# dashboard.net
KiCad netlist of a schematic drawn in EAGLE
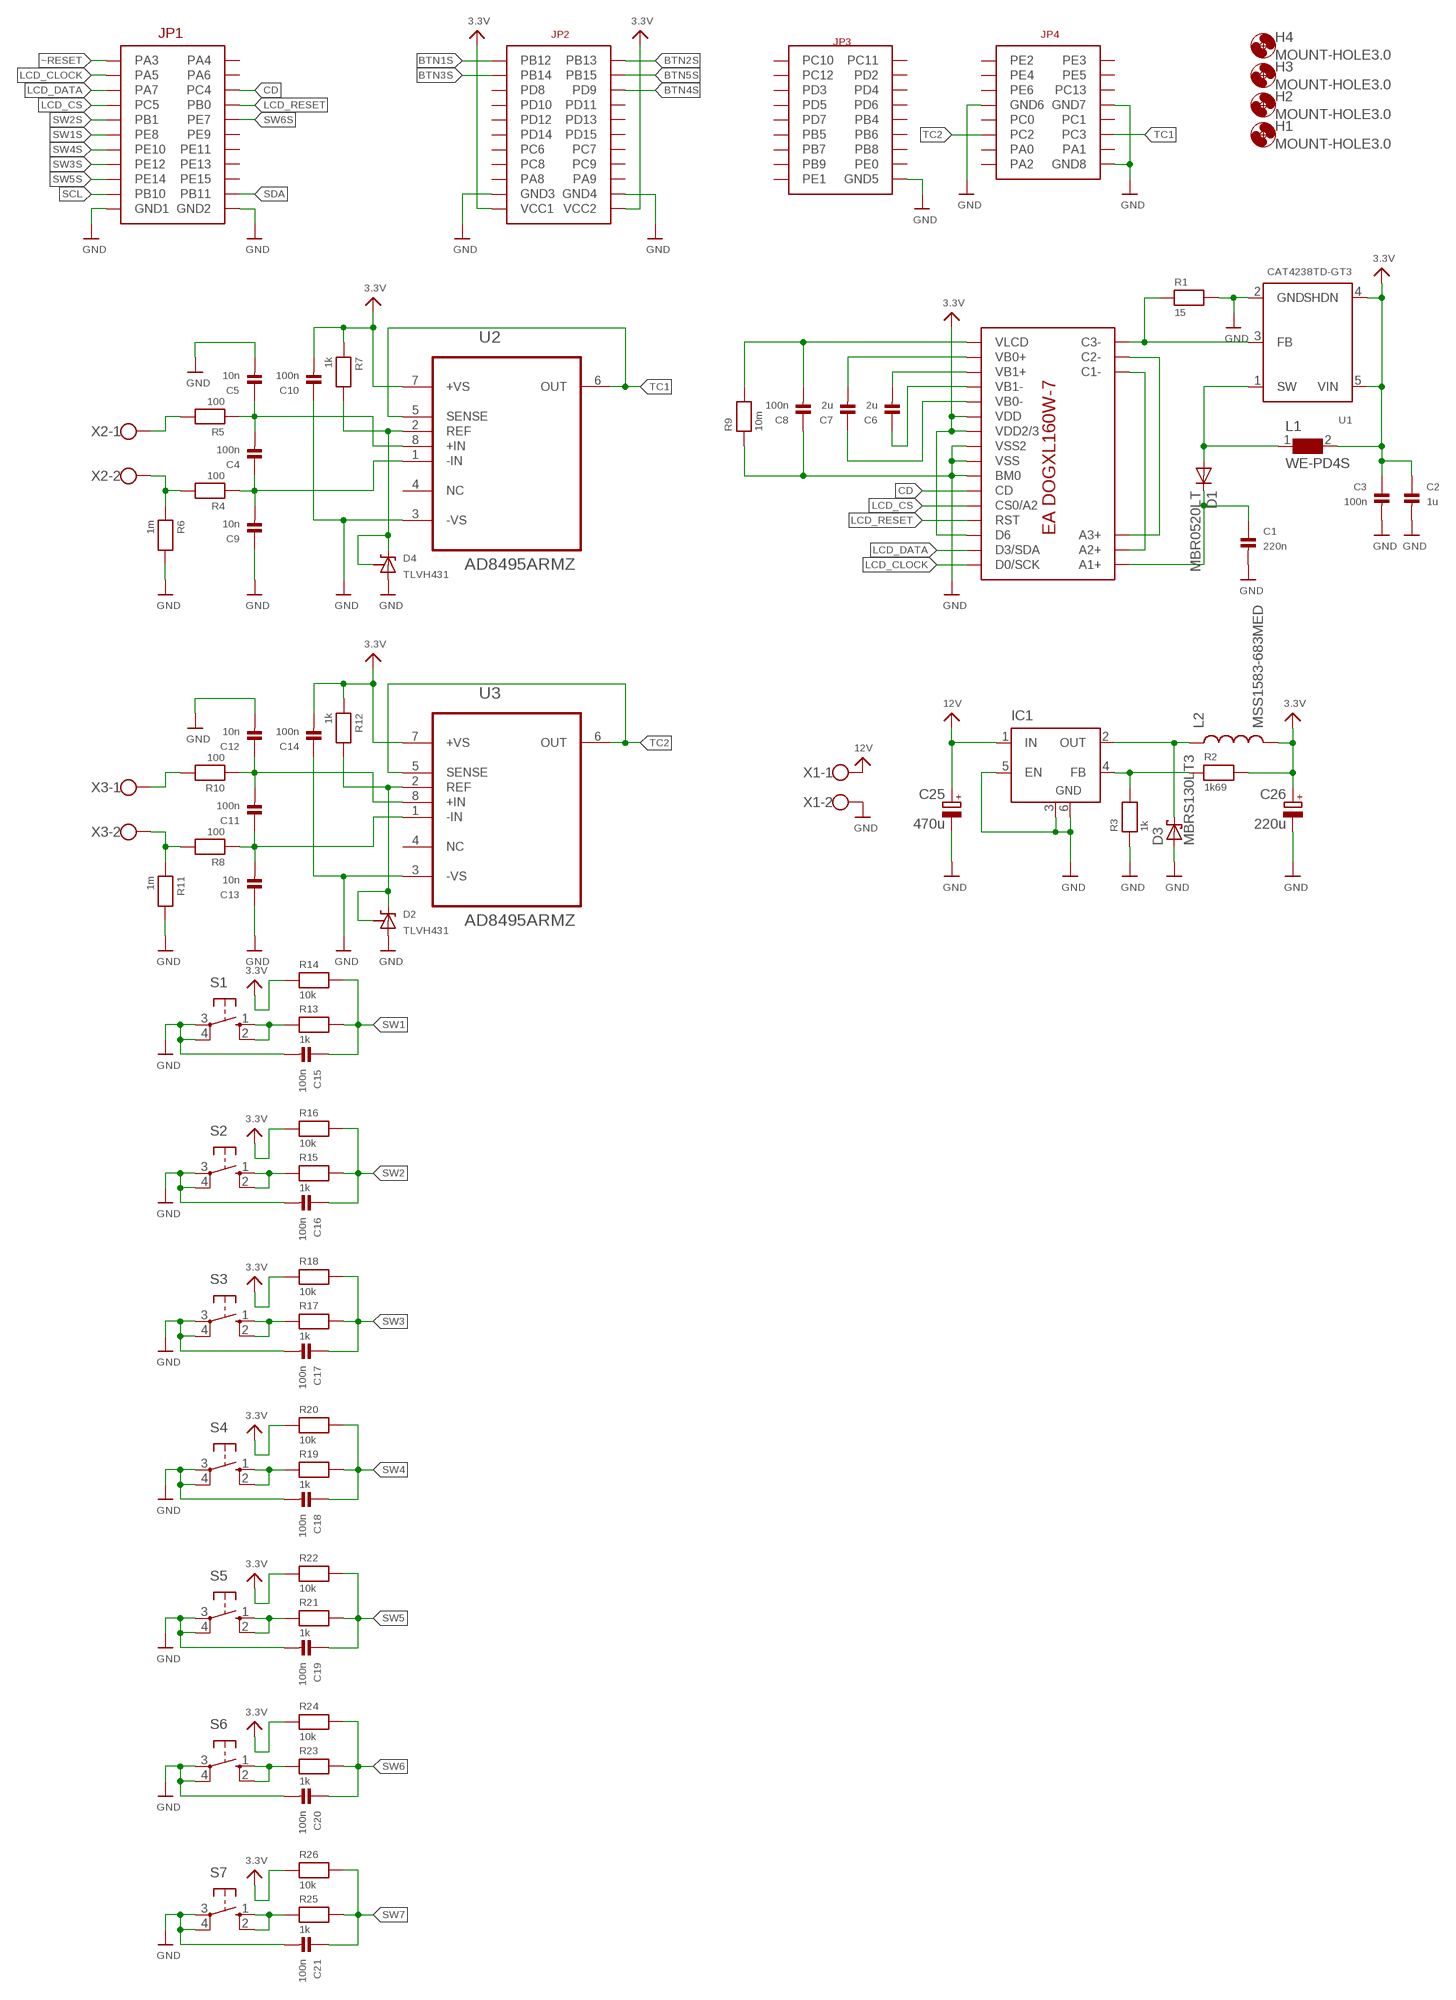
[diagram p0: schematic, sheet 1]

(export (version "E")
  (design (tool "Eeschema 10.0.6"))
  (components
    (comp (ref "C1")
      (value "220n")
      (footprint "eagle-import:_0805")
      (libsource (lib "eagle-import") (part "CAP_CERAMIC_0805"))
    )
    (comp (ref "C2")
      (value "1u")
      (footprint "eagle-import:_0805")
      (libsource (lib "eagle-import") (part "CAP_CERAMIC_0805"))
    )
    (comp (ref "C3")
      (value "100n")
      (footprint "eagle-import:_0603")
      (libsource (lib "eagle-import") (part "CAP_CERAMIC_0603"))
    )
    (comp (ref "C4")
      (value "100n")
      (footprint "eagle-import:_0603")
      (libsource (lib "eagle-import") (part "CAP_CERAMIC_0603"))
    )
    (comp (ref "C5")
      (value "10n")
      (footprint "eagle-import:_0603")
      (libsource (lib "eagle-import") (part "CAP_CERAMIC_0603"))
    )
    (comp (ref "C6")
      (value "2u")
      (footprint "eagle-import:_0805")
      (libsource (lib "eagle-import") (part "CAP_CERAMIC_0805"))
    )
    (comp (ref "C7")
      (value "2u")
      (footprint "eagle-import:_0805")
      (libsource (lib "eagle-import") (part "CAP_CERAMIC_0805"))
    )
    (comp (ref "C8")
      (value "100n")
      (footprint "eagle-import:_0603")
      (libsource (lib "eagle-import") (part "CAP_CERAMIC_0603"))
    )
    (comp (ref "C9")
      (value "10n")
      (footprint "eagle-import:_0603")
      (libsource (lib "eagle-import") (part "CAP_CERAMIC_0603"))
    )
    (comp (ref "C10")
      (value "100n")
      (footprint "eagle-import:_0603")
      (libsource (lib "eagle-import") (part "CAP_CERAMIC_0603"))
    )
    (comp (ref "C11")
      (value "100n")
      (footprint "eagle-import:_0603")
      (libsource (lib "eagle-import") (part "CAP_CERAMIC_0603"))
    )
    (comp (ref "C12")
      (value "10n")
      (footprint "eagle-import:_0603")
      (libsource (lib "eagle-import") (part "CAP_CERAMIC_0603"))
    )
    (comp (ref "C13")
      (value "10n")
      (footprint "eagle-import:_0603")
      (libsource (lib "eagle-import") (part "CAP_CERAMIC_0603"))
    )
    (comp (ref "C14")
      (value "100n")
      (footprint "eagle-import:_0603")
      (libsource (lib "eagle-import") (part "CAP_CERAMIC_0603"))
    )
    (comp (ref "C15")
      (value "100n")
      (footprint "eagle-import:_0603")
      (libsource (lib "eagle-import") (part "CAP_CERAMIC_0603"))
    )
    (comp (ref "C16")
      (value "100n")
      (footprint "eagle-import:_0603")
      (libsource (lib "eagle-import") (part "CAP_CERAMIC_0603"))
    )
    (comp (ref "C17")
      (value "100n")
      (footprint "eagle-import:_0603")
      (libsource (lib "eagle-import") (part "CAP_CERAMIC_0603"))
    )
    (comp (ref "C18")
      (value "100n")
      (footprint "eagle-import:_0603")
      (libsource (lib "eagle-import") (part "CAP_CERAMIC_0603"))
    )
    (comp (ref "C19")
      (value "100n")
      (footprint "eagle-import:_0603")
      (libsource (lib "eagle-import") (part "CAP_CERAMIC_0603"))
    )
    (comp (ref "C20")
      (value "100n")
      (footprint "eagle-import:_0603")
      (libsource (lib "eagle-import") (part "CAP_CERAMIC_0603"))
    )
    (comp (ref "C21")
      (value "100n")
      (footprint "eagle-import:_0603")
      (libsource (lib "eagle-import") (part "CAP_CERAMIC_0603"))
    )
    (comp (ref "C25")
      (value "470u")
      (footprint "eagle-import:153CLV-1012")
      (libsource (lib "eagle-import") (part "CPOL-EU153CLV-1012"))
    )
    (comp (ref "C26")
      (value "220u")
      (footprint "eagle-import:153CLV-1012")
      (libsource (lib "eagle-import") (part "CPOL-EU153CLV-1012"))
    )
    (comp (ref "D1")
      (value "MBR0520LT")
      (footprint "eagle-import:SOD123")
      (libsource (lib "eagle-import") (part "MBR0520LT"))
    )
    (comp (ref "D2")
      (value "TLVH431")
      (footprint "eagle-import:SOT23-R")
      (libsource (lib "eagle-import") (part "SHUNT-VREF"))
    )
    (comp (ref "D3")
      (value "MBRS130LT3")
      (footprint "eagle-import:SMB")
      (libsource (lib "eagle-import") (part "MBRS130LT3"))
    )
    (comp (ref "D4")
      (value "TLVH431")
      (footprint "eagle-import:SOT23-R")
      (libsource (lib "eagle-import") (part "SHUNT-VREF"))
    )
    (comp (ref "H1")
      (value "MOUNT-HOLE3.0")
      (footprint "eagle-import:3,0")
      (libsource (lib "eagle-import") (part "MOUNT-HOLE3.0"))
    )
    (comp (ref "H2")
      (value "MOUNT-HOLE3.0")
      (footprint "eagle-import:3,0")
      (libsource (lib "eagle-import") (part "MOUNT-HOLE3.0"))
    )
    (comp (ref "H3")
      (value "MOUNT-HOLE3.0")
      (footprint "eagle-import:3,0")
      (libsource (lib "eagle-import") (part "MOUNT-HOLE3.0"))
    )
    (comp (ref "H4")
      (value "MOUNT-HOLE3.0")
      (footprint "eagle-import:3,0")
      (libsource (lib "eagle-import") (part "MOUNT-HOLE3.0"))
    )
    (comp (ref "IC1")
      (value "LM2596S")
      (footprint "eagle-import:TO263-5")
      (libsource (lib "eagle-import") (part "LM2596S"))
    )
    (comp (ref "L1")
      (value "WE-PD4S")
      (footprint "eagle-import:S")
      (fields (field (name "MPN") "7445501"))
      (libsource (lib "eagle-import") (part "WE-PD4_S-7445501"))
    )
    (comp (ref "L2")
      (value "MSS1583-683MED")
      (footprint "eagle-import:CDRH125")
      (libsource (lib "eagle-import") (part "INDUCTORPWR"))
    )
    (comp (ref "R1")
      (value "15")
      (footprint "eagle-import:_0603")
      (libsource (lib "eagle-import") (part "RESISTOR_0603"))
    )
    (comp (ref "R2")
      (value "1k69")
      (footprint "eagle-import:_0603")
      (libsource (lib "eagle-import") (part "RESISTOR_0603"))
    )
    (comp (ref "R3")
      (value "1k")
      (footprint "eagle-import:_0603")
      (libsource (lib "eagle-import") (part "RESISTOR_0603"))
    )
    (comp (ref "R4")
      (value "100")
      (footprint "eagle-import:_0603")
      (libsource (lib "eagle-import") (part "RESISTOR_0603"))
    )
    (comp (ref "R5")
      (value "100")
      (footprint "eagle-import:_0603")
      (libsource (lib "eagle-import") (part "RESISTOR_0603"))
    )
    (comp (ref "R6")
      (value "1m")
      (footprint "eagle-import:_0603")
      (libsource (lib "eagle-import") (part "RESISTOR_0603"))
    )
    (comp (ref "R7")
      (value "1k")
      (footprint "eagle-import:_0603")
      (libsource (lib "eagle-import") (part "RESISTOR_0603"))
    )
    (comp (ref "R8")
      (value "100")
      (footprint "eagle-import:_0603")
      (libsource (lib "eagle-import") (part "RESISTOR_0603"))
    )
    (comp (ref "R9")
      (value "10m")
      (footprint "eagle-import:_0805")
      (libsource (lib "eagle-import") (part "RESISTOR_0805"))
    )
    (comp (ref "R10")
      (value "100")
      (footprint "eagle-import:_0603")
      (libsource (lib "eagle-import") (part "RESISTOR_0603"))
    )
    (comp (ref "R11")
      (value "1m")
      (footprint "eagle-import:_0603")
      (libsource (lib "eagle-import") (part "RESISTOR_0603"))
    )
    (comp (ref "R12")
      (value "1k")
      (footprint "eagle-import:_0603")
      (libsource (lib "eagle-import") (part "RESISTOR_0603"))
    )
    (comp (ref "R13")
      (value "1k")
      (footprint "eagle-import:_0603")
      (libsource (lib "eagle-import") (part "RESISTOR_0603"))
    )
    (comp (ref "R14")
      (value "10k")
      (footprint "eagle-import:_0603")
      (libsource (lib "eagle-import") (part "RESISTOR_0603"))
    )
    (comp (ref "R15")
      (value "1k")
      (footprint "eagle-import:_0603")
      (libsource (lib "eagle-import") (part "RESISTOR_0603"))
    )
    (comp (ref "R16")
      (value "10k")
      (footprint "eagle-import:_0603")
      (libsource (lib "eagle-import") (part "RESISTOR_0603"))
    )
    (comp (ref "R17")
      (value "1k")
      (footprint "eagle-import:_0603")
      (libsource (lib "eagle-import") (part "RESISTOR_0603"))
    )
    (comp (ref "R18")
      (value "10k")
      (footprint "eagle-import:_0603")
      (libsource (lib "eagle-import") (part "RESISTOR_0603"))
    )
    (comp (ref "R19")
      (value "1k")
      (footprint "eagle-import:_0603")
      (libsource (lib "eagle-import") (part "RESISTOR_0603"))
    )
    (comp (ref "R20")
      (value "10k")
      (footprint "eagle-import:_0603")
      (libsource (lib "eagle-import") (part "RESISTOR_0603"))
    )
    (comp (ref "R21")
      (value "1k")
      (footprint "eagle-import:_0603")
      (libsource (lib "eagle-import") (part "RESISTOR_0603"))
    )
    (comp (ref "R22")
      (value "10k")
      (footprint "eagle-import:_0603")
      (libsource (lib "eagle-import") (part "RESISTOR_0603"))
    )
    (comp (ref "R23")
      (value "1k")
      (footprint "eagle-import:_0603")
      (libsource (lib "eagle-import") (part "RESISTOR_0603"))
    )
    (comp (ref "R24")
      (value "10k")
      (footprint "eagle-import:_0603")
      (libsource (lib "eagle-import") (part "RESISTOR_0603"))
    )
    (comp (ref "R25")
      (value "1k")
      (footprint "eagle-import:_0603")
      (libsource (lib "eagle-import") (part "RESISTOR_0603"))
    )
    (comp (ref "R26")
      (value "10k")
      (footprint "eagle-import:_0603")
      (libsource (lib "eagle-import") (part "RESISTOR_0603"))
    )
    (comp (ref "S1")
      (value "10-XX")
      (footprint "eagle-import:B3F-10XX")
      (fields (field (name "MPN") "B3F-1000"))
      (libsource (lib "eagle-import") (part "10-XX"))
    )
    (comp (ref "S2")
      (value "10-XX")
      (footprint "eagle-import:B3F-10XX")
      (fields (field (name "MPN") "B3F-1000"))
      (libsource (lib "eagle-import") (part "10-XX"))
    )
    (comp (ref "S3")
      (value "10-XX")
      (footprint "eagle-import:B3F-10XX")
      (fields (field (name "MPN") "B3F-1000"))
      (libsource (lib "eagle-import") (part "10-XX"))
    )
    (comp (ref "S4")
      (value "10-XX")
      (footprint "eagle-import:B3F-10XX")
      (fields (field (name "MPN") "B3F-1000"))
      (libsource (lib "eagle-import") (part "10-XX"))
    )
    (comp (ref "S5")
      (value "10-XX")
      (footprint "eagle-import:B3F-10XX")
      (fields (field (name "MPN") "B3F-1000"))
      (libsource (lib "eagle-import") (part "10-XX"))
    )
    (comp (ref "S6")
      (value "10-XX")
      (footprint "eagle-import:B3F-10XX")
      (fields (field (name "MPN") "B3F-1000"))
      (libsource (lib "eagle-import") (part "10-XX"))
    )
    (comp (ref "S7")
      (value "10-XX")
      (footprint "eagle-import:B3F-10XX")
      (fields (field (name "MPN") "B3F-1000"))
      (libsource (lib "eagle-import") (part "10-XX"))
    )
    (comp (ref "U$1")
      (value "CPU-BOARD")
      (footprint "eagle-import:CPU-BOARD-JP1")
      (libsource (lib "eagle-import") (part "CPU-BOARD"))
    )
    (comp (ref "U$10")
      (value "EA-DOGXL160W-7")
      (footprint "eagle-import:EA-DOGXL160W-7")
      (libsource (lib "eagle-import") (part "EA-DOGXL160W-7"))
    )
    (comp (ref "U1")
      (value "CAT4238TD-GT3")
      (footprint "eagle-import:SOT23-5")
      (libsource (lib "eagle-import") (part "FAN5331"))
    )
    (comp (ref "U2")
      (value "AD8495ARMZ")
      (footprint "eagle-import:SOP65P490X110-8N")
      (libsource (lib "eagle-import") (part "AD8495ARMZ"))
    )
    (comp (ref "U3")
      (value "AD8495ARMZ")
      (footprint "eagle-import:SOP65P490X110-8N")
      (libsource (lib "eagle-import") (part "AD8495ARMZ"))
    )
    (comp (ref "X1")
      (value "W237-102")
      (footprint "eagle-import:W237-102")
      (fields (field (name "MPN") "237-102"))
      (libsource (lib "eagle-import") (part "W237-102"))
    )
    (comp (ref "X2")
      (value "W237-102")
      (footprint "eagle-import:W237-102")
      (fields (field (name "MPN") "237-102"))
      (libsource (lib "eagle-import") (part "W237-102"))
    )
    (comp (ref "X3")
      (value "W237-102")
      (footprint "eagle-import:W237-102")
      (fields (field (name "MPN") "237-102"))
      (libsource (lib "eagle-import") (part "W237-102"))
    )
  )
  (nets
    (net (code "1") (name "/~{RESET}") (class "Default")
      (node (ref "U$1") (pin "P$1") (pinfunction "PA3_P$1") (pintype "bidirectional"))
    )
    (net (code "2") (name "3.3V") (class "Default")
      (node (ref "C10") (pin "2") (pinfunction "P$2_2") (pintype "passive"))
      (node (ref "C14") (pin "2") (pinfunction "P$2_2") (pintype "passive"))
      (node (ref "C2") (pin "1") (pinfunction "P$1_1") (pintype "passive"))
      (node (ref "C26") (pin "+") (pinfunction "+_+") (pintype "passive"))
      (node (ref "C3") (pin "1") (pinfunction "P$1_1") (pintype "passive"))
      (node (ref "L1") (pin "2") (pinfunction "2_2") (pintype "passive"))
      (node (ref "L2") (pin "2") (pinfunction "2_2") (pintype "passive"))
      (node (ref "R12") (pin "1") (pinfunction "1_1") (pintype "passive"))
      (node (ref "R14") (pin "1") (pinfunction "1_1") (pintype "passive"))
      (node (ref "R16") (pin "1") (pinfunction "1_1") (pintype "passive"))
      (node (ref "R18") (pin "1") (pinfunction "1_1") (pintype "passive"))
      (node (ref "R2") (pin "2") (pinfunction "2_2") (pintype "passive"))
      (node (ref "R20") (pin "1") (pinfunction "1_1") (pintype "passive"))
      (node (ref "R22") (pin "1") (pinfunction "1_1") (pintype "passive"))
      (node (ref "R24") (pin "1") (pinfunction "1_1") (pintype "passive"))
      (node (ref "R26") (pin "1") (pinfunction "1_1") (pintype "passive"))
      (node (ref "R7") (pin "1") (pinfunction "1_1") (pintype "passive"))
      (node (ref "U$1") (pin "P$43") (pinfunction "VCC1_P$43") (pintype "bidirectional"))
      (node (ref "U$1") (pin "P$44") (pinfunction "VCC2_P$44") (pintype "bidirectional"))
      (node (ref "U$10") (pin "P$22") (pinfunction "VDD_P$22") (pintype "bidirectional"))
      (node (ref "U$10") (pin "P$23") (pinfunction "VDD2/3_P$23") (pintype "bidirectional"))
      (node (ref "U$10") (pin "P$30") (pinfunction "D6_P$30") (pintype "bidirectional"))
      (node (ref "U1") (pin "4") (pinfunction "SHDN_4") (pintype "bidirectional"))
      (node (ref "U1") (pin "5") (pinfunction "VIN_5") (pintype "bidirectional"))
      (node (ref "U2") (pin "7") (pinfunction "+VS_7") (pintype "power_in"))
      (node (ref "U3") (pin "7") (pinfunction "+VS_7") (pintype "power_in"))
    )
    (net (code "3") (name "12V") (class "Default")
      (node (ref "C25") (pin "+") (pinfunction "+_+") (pintype "passive"))
      (node (ref "IC1") (pin "1") (pinfunction "IN_1") (pintype "input"))
      (node (ref "X1") (pin "1") (pinfunction "KL_1") (pintype "passive"))
    )
    (net (code "4") (name "BTN1S") (class "Default")
      (node (ref "U$1") (pin "P$23") (pinfunction "PB12_P$23") (pintype "bidirectional"))
    )
    (net (code "5") (name "BTN2S") (class "Default")
      (node (ref "U$1") (pin "P$24") (pinfunction "PB13_P$24") (pintype "bidirectional"))
    )
    (net (code "6") (name "BTN3S") (class "Default")
      (node (ref "U$1") (pin "P$25") (pinfunction "PB14_P$25") (pintype "bidirectional"))
    )
    (net (code "7") (name "BTN4S") (class "Default")
      (node (ref "U$1") (pin "P$28") (pinfunction "PD9_P$28") (pintype "bidirectional"))
    )
    (net (code "8") (name "BTN5S") (class "Default")
      (node (ref "U$1") (pin "P$26") (pinfunction "PB15_P$26") (pintype "bidirectional"))
    )
    (net (code "9") (name "CD") (class "Default")
      (node (ref "U$1") (pin "P$6") (pinfunction "PC4_P$6") (pintype "bidirectional"))
      (node (ref "U$10") (pin "P$27") (pinfunction "CD_P$27") (pintype "bidirectional"))
    )
    (net (code "10") (name "GND") (class "Default")
      (node (ref "C1") (pin "2") (pinfunction "P$2_2") (pintype "passive"))
      (node (ref "C10") (pin "1") (pinfunction "P$1_1") (pintype "passive"))
      (node (ref "C12") (pin "2") (pinfunction "P$2_2") (pintype "passive"))
      (node (ref "C13") (pin "1") (pinfunction "P$1_1") (pintype "passive"))
      (node (ref "C14") (pin "1") (pinfunction "P$1_1") (pintype "passive"))
      (node (ref "C15") (pin "2") (pinfunction "P$2_2") (pintype "passive"))
      (node (ref "C16") (pin "2") (pinfunction "P$2_2") (pintype "passive"))
      (node (ref "C17") (pin "2") (pinfunction "P$2_2") (pintype "passive"))
      (node (ref "C18") (pin "2") (pinfunction "P$2_2") (pintype "passive"))
      (node (ref "C19") (pin "2") (pinfunction "P$2_2") (pintype "passive"))
      (node (ref "C2") (pin "2") (pinfunction "P$2_2") (pintype "passive"))
      (node (ref "C20") (pin "2") (pinfunction "P$2_2") (pintype "passive"))
      (node (ref "C21") (pin "2") (pinfunction "P$2_2") (pintype "passive"))
      (node (ref "C25") (pin "-") (pinfunction "-_-") (pintype "passive"))
      (node (ref "C26") (pin "-") (pinfunction "-_-") (pintype "passive"))
      (node (ref "C3") (pin "2") (pinfunction "P$2_2") (pintype "passive"))
      (node (ref "C5") (pin "2") (pinfunction "P$2_2") (pintype "passive"))
      (node (ref "C8") (pin "1") (pinfunction "P$1_1") (pintype "passive"))
      (node (ref "C9") (pin "1") (pinfunction "P$1_1") (pintype "passive"))
      (node (ref "D2") (pin "3") (pinfunction "A_3") (pintype "passive"))
      (node (ref "D3") (pin "A") (pinfunction "A_A") (pintype "passive"))
      (node (ref "D4") (pin "3") (pinfunction "A_3") (pintype "passive"))
      (node (ref "IC1") (pin "3") (pinfunction "GND_3") (pintype "power_in"))
      (node (ref "IC1") (pin "5") (pinfunction "EN_5") (pintype "input"))
      (node (ref "IC1") (pin "6") (pinfunction "GND_6") (pintype "power_in"))
      (node (ref "R1") (pin "2") (pinfunction "2_2") (pintype "passive"))
      (node (ref "R11") (pin "2") (pinfunction "2_2") (pintype "passive"))
      (node (ref "R3") (pin "1") (pinfunction "1_1") (pintype "passive"))
      (node (ref "R6") (pin "2") (pinfunction "2_2") (pintype "passive"))
      (node (ref "R9") (pin "1") (pinfunction "1_1") (pintype "passive"))
      (node (ref "S1") (pin "3") (pinfunction "P_3") (pintype "passive"))
      (node (ref "S1") (pin "4") (pinfunction "P1_4") (pintype "passive"))
      (node (ref "S2") (pin "3") (pinfunction "P_3") (pintype "passive"))
      (node (ref "S2") (pin "4") (pinfunction "P1_4") (pintype "passive"))
      (node (ref "S3") (pin "3") (pinfunction "P_3") (pintype "passive"))
      (node (ref "S3") (pin "4") (pinfunction "P1_4") (pintype "passive"))
      (node (ref "S4") (pin "3") (pinfunction "P_3") (pintype "passive"))
      (node (ref "S4") (pin "4") (pinfunction "P1_4") (pintype "passive"))
      (node (ref "S5") (pin "3") (pinfunction "P_3") (pintype "passive"))
      (node (ref "S5") (pin "4") (pinfunction "P1_4") (pintype "passive"))
      (node (ref "S6") (pin "3") (pinfunction "P_3") (pintype "passive"))
      (node (ref "S6") (pin "4") (pinfunction "P1_4") (pintype "passive"))
      (node (ref "S7") (pin "3") (pinfunction "P_3") (pintype "passive"))
      (node (ref "S7") (pin "4") (pinfunction "P1_4") (pintype "passive"))
      (node (ref "U$1") (pin "P$19") (pinfunction "GND1_P$19") (pintype "bidirectional"))
      (node (ref "U$1") (pin "P$20") (pinfunction "GND2_P$20") (pintype "bidirectional"))
      (node (ref "U$1") (pin "P$41") (pinfunction "GND3_P$41") (pintype "bidirectional"))
      (node (ref "U$1") (pin "P$42") (pinfunction "GND4_P$42") (pintype "bidirectional"))
      (node (ref "U$1") (pin "P$62") (pinfunction "GND5_P$62") (pintype "bidirectional"))
      (node (ref "U$1") (pin "P$69") (pinfunction "GND6_P$69") (pintype "bidirectional"))
      (node (ref "U$1") (pin "P$70") (pinfunction "GND7_P$70") (pintype "bidirectional"))
      (node (ref "U$1") (pin "P$78") (pinfunction "GND8_P$78") (pintype "bidirectional"))
      (node (ref "U$10") (pin "P$24") (pinfunction "VSS2_P$24") (pintype "bidirectional"))
      (node (ref "U$10") (pin "P$25") (pinfunction "VSS_P$25") (pintype "bidirectional"))
      (node (ref "U$10") (pin "P$26") (pinfunction "BM0_P$26") (pintype "bidirectional"))
      (node (ref "U1") (pin "2") (pinfunction "GND_2") (pintype "bidirectional"))
      (node (ref "U2") (pin "3") (pinfunction "-VS_3") (pintype "power_in"))
      (node (ref "U3") (pin "3") (pinfunction "-VS_3") (pintype "power_in"))
      (node (ref "X1") (pin "2") (pinfunction "KL_2") (pintype "passive"))
    )
    (net (code "11") (name "LCD_CLOCK") (class "Default")
      (node (ref "U$1") (pin "P$3") (pinfunction "PA5_P$3") (pintype "bidirectional"))
      (node (ref "U$10") (pin "P$32") (pinfunction "D0/SCK_P$32") (pintype "bidirectional"))
    )
    (net (code "12") (name "LCD_CS") (class "Default")
      (node (ref "U$1") (pin "P$7") (pinfunction "PC5_P$7") (pintype "bidirectional"))
      (node (ref "U$10") (pin "P$28") (pinfunction "CS0/A2_P$28") (pintype "bidirectional"))
    )
    (net (code "13") (name "LCD_DATA") (class "Default")
      (node (ref "U$1") (pin "P$5") (pinfunction "PA7_P$5") (pintype "bidirectional"))
      (node (ref "U$10") (pin "P$31") (pinfunction "D3/SDA_P$31") (pintype "bidirectional"))
    )
    (net (code "14") (name "LCD_RESET") (class "Default")
      (node (ref "U$1") (pin "P$8") (pinfunction "PB0_P$8") (pintype "bidirectional"))
      (node (ref "U$10") (pin "P$29") (pinfunction "RST_P$29") (pintype "bidirectional"))
    )
    (net (code "15") (name "Net-(C1-P$1)") (class "Default")
      (node (ref "C1") (pin "1") (pinfunction "P$1_1") (pintype "passive"))
      (node (ref "D1") (pin "C") (pinfunction "C_C") (pintype "passive"))
      (node (ref "U$10") (pin "P$1") (pinfunction "A1+_P$1") (pintype "bidirectional"))
    )
    (net (code "16") (name "Net-(C4-P$1)") (class "Default")
      (node (ref "C4") (pin "1") (pinfunction "P$1_1") (pintype "passive"))
      (node (ref "C9") (pin "2") (pinfunction "P$2_2") (pintype "passive"))
      (node (ref "R4") (pin "1") (pinfunction "1_1") (pintype "passive"))
      (node (ref "U2") (pin "1") (pinfunction "-IN_1") (pintype "input"))
    )
    (net (code "17") (name "Net-(C4-P$2)") (class "Default")
      (node (ref "C4") (pin "2") (pinfunction "P$2_2") (pintype "passive"))
      (node (ref "C5") (pin "1") (pinfunction "P$1_1") (pintype "passive"))
      (node (ref "R5") (pin "1") (pinfunction "1_1") (pintype "passive"))
      (node (ref "U2") (pin "8") (pinfunction "+IN_8") (pintype "input"))
    )
    (net (code "18") (name "Net-(C6-P$1)") (class "Default")
      (node (ref "C6") (pin "1") (pinfunction "P$1_1") (pintype "passive"))
      (node (ref "U$10") (pin "P$20") (pinfunction "VB1-_P$20") (pintype "bidirectional"))
    )
    (net (code "19") (name "Net-(C6-P$2)") (class "Default")
      (node (ref "C6") (pin "2") (pinfunction "P$2_2") (pintype "passive"))
      (node (ref "U$10") (pin "P$19") (pinfunction "VB1+_P$19") (pintype "bidirectional"))
    )
    (net (code "20") (name "Net-(C7-P$1)") (class "Default")
      (node (ref "C7") (pin "1") (pinfunction "P$1_1") (pintype "passive"))
      (node (ref "U$10") (pin "P$21") (pinfunction "VB0-_P$21") (pintype "bidirectional"))
    )
    (net (code "21") (name "Net-(C7-P$2)") (class "Default")
      (node (ref "C7") (pin "2") (pinfunction "P$2_2") (pintype "passive"))
      (node (ref "U$10") (pin "P$18") (pinfunction "VB0+_P$18") (pintype "bidirectional"))
    )
    (net (code "22") (name "Net-(C8-P$2)") (class "Default")
      (node (ref "C8") (pin "2") (pinfunction "P$2_2") (pintype "passive"))
      (node (ref "R9") (pin "2") (pinfunction "2_2") (pintype "passive"))
      (node (ref "U$10") (pin "P$17") (pinfunction "VLCD_P$17") (pintype "bidirectional"))
    )
    (net (code "23") (name "Net-(C11-P$1)") (class "Default")
      (node (ref "C11") (pin "1") (pinfunction "P$1_1") (pintype "passive"))
      (node (ref "C13") (pin "2") (pinfunction "P$2_2") (pintype "passive"))
      (node (ref "R8") (pin "1") (pinfunction "1_1") (pintype "passive"))
      (node (ref "U3") (pin "1") (pinfunction "-IN_1") (pintype "input"))
    )
    (net (code "24") (name "Net-(C11-P$2)") (class "Default")
      (node (ref "C11") (pin "2") (pinfunction "P$2_2") (pintype "passive"))
      (node (ref "C12") (pin "1") (pinfunction "P$1_1") (pintype "passive"))
      (node (ref "R10") (pin "1") (pinfunction "1_1") (pintype "passive"))
      (node (ref "U3") (pin "8") (pinfunction "+IN_8") (pintype "input"))
    )
    (net (code "25") (name "Net-(D2-C)") (class "Default")
      (node (ref "D2") (pin "1") (pinfunction "VREF_1") (pintype "passive"))
      (node (ref "D2") (pin "2") (pinfunction "C_2") (pintype "passive"))
      (node (ref "R12") (pin "2") (pinfunction "2_2") (pintype "passive"))
      (node (ref "U3") (pin "2") (pinfunction "REF_2") (pintype "input"))
    )
    (net (code "26") (name "Net-(D4-C)") (class "Default")
      (node (ref "D4") (pin "1") (pinfunction "VREF_1") (pintype "passive"))
      (node (ref "D4") (pin "2") (pinfunction "C_2") (pintype "passive"))
      (node (ref "R7") (pin "2") (pinfunction "2_2") (pintype "passive"))
      (node (ref "U2") (pin "2") (pinfunction "REF_2") (pintype "input"))
    )
    (net (code "27") (name "Net-(IC1-FB)") (class "Default")
      (node (ref "IC1") (pin "4") (pinfunction "FB_4") (pintype "input"))
      (node (ref "R2") (pin "1") (pinfunction "1_1") (pintype "passive"))
      (node (ref "R3") (pin "2") (pinfunction "2_2") (pintype "passive"))
    )
    (net (code "28") (name "Net-(IC1-OUT)") (class "Default")
      (node (ref "D3") (pin "C") (pinfunction "C_C") (pintype "passive"))
      (node (ref "IC1") (pin "2") (pinfunction "OUT_2") (pintype "output"))
      (node (ref "L2") (pin "1") (pinfunction "1_1") (pintype "passive"))
    )
    (net (code "29") (name "Net-(S1-S)") (class "Default")
      (node (ref "R13") (pin "1") (pinfunction "1_1") (pintype "passive"))
      (node (ref "S1") (pin "1") (pinfunction "S_1") (pintype "passive"))
      (node (ref "S1") (pin "2") (pinfunction "S1_2") (pintype "passive"))
    )
    (net (code "30") (name "Net-(S2-S)") (class "Default")
      (node (ref "R15") (pin "1") (pinfunction "1_1") (pintype "passive"))
      (node (ref "S2") (pin "1") (pinfunction "S_1") (pintype "passive"))
      (node (ref "S2") (pin "2") (pinfunction "S1_2") (pintype "passive"))
    )
    (net (code "31") (name "Net-(S3-S)") (class "Default")
      (node (ref "R17") (pin "1") (pinfunction "1_1") (pintype "passive"))
      (node (ref "S3") (pin "1") (pinfunction "S_1") (pintype "passive"))
      (node (ref "S3") (pin "2") (pinfunction "S1_2") (pintype "passive"))
    )
    (net (code "32") (name "Net-(S4-S)") (class "Default")
      (node (ref "R19") (pin "1") (pinfunction "1_1") (pintype "passive"))
      (node (ref "S4") (pin "1") (pinfunction "S_1") (pintype "passive"))
      (node (ref "S4") (pin "2") (pinfunction "S1_2") (pintype "passive"))
    )
    (net (code "33") (name "Net-(S5-S)") (class "Default")
      (node (ref "R21") (pin "1") (pinfunction "1_1") (pintype "passive"))
      (node (ref "S5") (pin "1") (pinfunction "S_1") (pintype "passive"))
      (node (ref "S5") (pin "2") (pinfunction "S1_2") (pintype "passive"))
    )
    (net (code "34") (name "Net-(S6-S)") (class "Default")
      (node (ref "R23") (pin "1") (pinfunction "1_1") (pintype "passive"))
      (node (ref "S6") (pin "1") (pinfunction "S_1") (pintype "passive"))
      (node (ref "S6") (pin "2") (pinfunction "S1_2") (pintype "passive"))
    )
    (net (code "35") (name "Net-(S7-S)") (class "Default")
      (node (ref "R25") (pin "1") (pinfunction "1_1") (pintype "passive"))
      (node (ref "S7") (pin "1") (pinfunction "S_1") (pintype "passive"))
      (node (ref "S7") (pin "2") (pinfunction "S1_2") (pintype "passive"))
    )
    (net (code "36") (name "Net-(U$10-A2+)") (class "Default")
      (node (ref "U$10") (pin "P$14") (pinfunction "C1-_P$14") (pintype "bidirectional"))
      (node (ref "U$10") (pin "P$2") (pinfunction "A2+_P$2") (pintype "bidirectional"))
    )
    (net (code "37") (name "Net-(U$10-A3+)") (class "Default")
      (node (ref "U$10") (pin "P$15") (pinfunction "C2-_P$15") (pintype "bidirectional"))
      (node (ref "U$10") (pin "P$3") (pinfunction "A3+_P$3") (pintype "bidirectional"))
    )
    (net (code "38") (name "Net-(U$10-C3-)") (class "Default")
      (node (ref "R1") (pin "1") (pinfunction "1_1") (pintype "passive"))
      (node (ref "U$10") (pin "P$16") (pinfunction "C3-_P$16") (pintype "bidirectional"))
      (node (ref "U1") (pin "3") (pinfunction "FB_3") (pintype "bidirectional"))
    )
    (net (code "39") (name "Net-(U1-SW)") (class "Default")
      (node (ref "D1") (pin "A") (pinfunction "A_A") (pintype "passive"))
      (node (ref "L1") (pin "1") (pinfunction "1_1") (pintype "passive"))
      (node (ref "U1") (pin "1") (pinfunction "SW_1") (pintype "bidirectional"))
    )
    (net (code "40") (name "Net-(X2A-KL)") (class "Default")
      (node (ref "R5") (pin "2") (pinfunction "2_2") (pintype "passive"))
      (node (ref "X2") (pin "1") (pinfunction "KL_1") (pintype "passive"))
    )
    (net (code "41") (name "Net-(X2B-KL)") (class "Default")
      (node (ref "R4") (pin "2") (pinfunction "2_2") (pintype "passive"))
      (node (ref "R6") (pin "1") (pinfunction "1_1") (pintype "passive"))
      (node (ref "X2") (pin "2") (pinfunction "KL_2") (pintype "passive"))
    )
    (net (code "42") (name "Net-(X3A-KL)") (class "Default")
      (node (ref "R10") (pin "2") (pinfunction "2_2") (pintype "passive"))
      (node (ref "X3") (pin "1") (pinfunction "KL_1") (pintype "passive"))
    )
    (net (code "43") (name "Net-(X3B-KL)") (class "Default")
      (node (ref "R11") (pin "1") (pinfunction "1_1") (pintype "passive"))
      (node (ref "R8") (pin "2") (pinfunction "2_2") (pintype "passive"))
      (node (ref "X3") (pin "2") (pinfunction "KL_2") (pintype "passive"))
    )
    (net (code "44") (name "SCL") (class "Default")
      (node (ref "U$1") (pin "P$21") (pinfunction "PB10_P$21") (pintype "bidirectional"))
    )
    (net (code "45") (name "SDA") (class "Default")
      (node (ref "U$1") (pin "P$22") (pinfunction "PB11_P$22") (pintype "bidirectional"))
    )
    (net (code "46") (name "SW1") (class "Default")
      (node (ref "C15") (pin "1") (pinfunction "P$1_1") (pintype "passive"))
      (node (ref "R13") (pin "2") (pinfunction "2_2") (pintype "passive"))
      (node (ref "R14") (pin "2") (pinfunction "2_2") (pintype "passive"))
    )
    (net (code "47") (name "SW1S") (class "Default")
      (node (ref "U$1") (pin "P$11") (pinfunction "PE8_P$11") (pintype "bidirectional"))
    )
    (net (code "48") (name "SW2") (class "Default")
      (node (ref "C16") (pin "1") (pinfunction "P$1_1") (pintype "passive"))
      (node (ref "R15") (pin "2") (pinfunction "2_2") (pintype "passive"))
      (node (ref "R16") (pin "2") (pinfunction "2_2") (pintype "passive"))
    )
    (net (code "49") (name "SW2S") (class "Default")
      (node (ref "U$1") (pin "P$9") (pinfunction "PB1_P$9") (pintype "bidirectional"))
    )
    (net (code "50") (name "SW3") (class "Default")
      (node (ref "C17") (pin "1") (pinfunction "P$1_1") (pintype "passive"))
      (node (ref "R17") (pin "2") (pinfunction "2_2") (pintype "passive"))
      (node (ref "R18") (pin "2") (pinfunction "2_2") (pintype "passive"))
    )
    (net (code "51") (name "SW3S") (class "Default")
      (node (ref "U$1") (pin "P$15") (pinfunction "PE12_P$15") (pintype "bidirectional"))
    )
    (net (code "52") (name "SW4") (class "Default")
      (node (ref "C18") (pin "1") (pinfunction "P$1_1") (pintype "passive"))
      (node (ref "R19") (pin "2") (pinfunction "2_2") (pintype "passive"))
      (node (ref "R20") (pin "2") (pinfunction "2_2") (pintype "passive"))
    )
    (net (code "53") (name "SW4S") (class "Default")
      (node (ref "U$1") (pin "P$13") (pinfunction "PE10_P$13") (pintype "bidirectional"))
    )
    (net (code "54") (name "SW5") (class "Default")
      (node (ref "C19") (pin "1") (pinfunction "P$1_1") (pintype "passive"))
      (node (ref "R21") (pin "2") (pinfunction "2_2") (pintype "passive"))
      (node (ref "R22") (pin "2") (pinfunction "2_2") (pintype "passive"))
    )
    (net (code "55") (name "SW5S") (class "Default")
      (node (ref "U$1") (pin "P$17") (pinfunction "PE14_P$17") (pintype "bidirectional"))
    )
    (net (code "56") (name "SW6") (class "Default")
      (node (ref "C20") (pin "1") (pinfunction "P$1_1") (pintype "passive"))
      (node (ref "R23") (pin "2") (pinfunction "2_2") (pintype "passive"))
      (node (ref "R24") (pin "2") (pinfunction "2_2") (pintype "passive"))
    )
    (net (code "57") (name "SW6S") (class "Default")
      (node (ref "U$1") (pin "P$10") (pinfunction "PE7_P$10") (pintype "bidirectional"))
    )
    (net (code "58") (name "SW7") (class "Default")
      (node (ref "C21") (pin "1") (pinfunction "P$1_1") (pintype "passive"))
      (node (ref "R25") (pin "2") (pinfunction "2_2") (pintype "passive"))
      (node (ref "R26") (pin "2") (pinfunction "2_2") (pintype "passive"))
    )
    (net (code "59") (name "TC1") (class "Default")
      (node (ref "U$1") (pin "P$74") (pinfunction "PC3_P$74") (pintype "bidirectional"))
      (node (ref "U2") (pin "5") (pinfunction "SENSE_5") (pintype "input"))
      (node (ref "U2") (pin "6") (pinfunction "OUT_6") (pintype "output"))
    )
    (net (code "60") (name "TC2") (class "Default")
      (node (ref "U$1") (pin "P$73") (pinfunction "PC2_P$73") (pintype "bidirectional"))
      (node (ref "U3") (pin "5") (pinfunction "SENSE_5") (pintype "input"))
      (node (ref "U3") (pin "6") (pinfunction "OUT_6") (pintype "output"))
    )
    (net (code "61") (name "unconnected-(U$1A-PA4-PadP$2)") (class "Default")
      (node (ref "U$1") (pin "P$2") (pinfunction "PA4_P$2") (pintype "bidirectional"))
    )
    (net (code "62") (name "unconnected-(U$1A-PA6-PadP$4)") (class "Default")
      (node (ref "U$1") (pin "P$4") (pinfunction "PA6_P$4") (pintype "bidirectional"))
    )
    (net (code "63") (name "unconnected-(U$1A-PE9-PadP$12)") (class "Default")
      (node (ref "U$1") (pin "P$12") (pinfunction "PE9_P$12") (pintype "bidirectional"))
    )
    (net (code "64") (name "unconnected-(U$1A-PE11-PadP$14)") (class "Default")
      (node (ref "U$1") (pin "P$14") (pinfunction "PE11_P$14") (pintype "bidirectional"))
    )
    (net (code "65") (name "unconnected-(U$1A-PE13-PadP$16)") (class "Default")
      (node (ref "U$1") (pin "P$16") (pinfunction "PE13_P$16") (pintype "bidirectional"))
    )
    (net (code "66") (name "unconnected-(U$1A-PE15-PadP$18)") (class "Default")
      (node (ref "U$1") (pin "P$18") (pinfunction "PE15_P$18") (pintype "bidirectional"))
    )
    (net (code "67") (name "unconnected-(U$1B-PA8-PadP$39)") (class "Default")
      (node (ref "U$1") (pin "P$39") (pinfunction "PA8_P$39") (pintype "bidirectional"))
    )
    (net (code "68") (name "unconnected-(U$1B-PA9-PadP$40)") (class "Default")
      (node (ref "U$1") (pin "P$40") (pinfunction "PA9_P$40") (pintype "bidirectional"))
    )
    (net (code "69") (name "unconnected-(U$1B-PC6-PadP$35)") (class "Default")
      (node (ref "U$1") (pin "P$35") (pinfunction "PC6_P$35") (pintype "bidirectional"))
    )
    (net (code "70") (name "unconnected-(U$1B-PC7-PadP$36)") (class "Default")
      (node (ref "U$1") (pin "P$36") (pinfunction "PC7_P$36") (pintype "bidirectional"))
    )
    (net (code "71") (name "unconnected-(U$1B-PC8-PadP$37)") (class "Default")
      (node (ref "U$1") (pin "P$37") (pinfunction "PC8_P$37") (pintype "bidirectional"))
    )
    (net (code "72") (name "unconnected-(U$1B-PC9-PadP$38)") (class "Default")
      (node (ref "U$1") (pin "P$38") (pinfunction "PC9_P$38") (pintype "bidirectional"))
    )
    (net (code "73") (name "unconnected-(U$1B-PD8-PadP$27)") (class "Default")
      (node (ref "U$1") (pin "P$27") (pinfunction "PD8_P$27") (pintype "bidirectional"))
    )
    (net (code "74") (name "unconnected-(U$1B-PD10-PadP$29)") (class "Default")
      (node (ref "U$1") (pin "P$29") (pinfunction "PD10_P$29") (pintype "bidirectional"))
    )
    (net (code "75") (name "unconnected-(U$1B-PD11-PadP$30)") (class "Default")
      (node (ref "U$1") (pin "P$30") (pinfunction "PD11_P$30") (pintype "bidirectional"))
    )
    (net (code "76") (name "unconnected-(U$1B-PD12-PadP$31)") (class "Default")
      (node (ref "U$1") (pin "P$31") (pinfunction "PD12_P$31") (pintype "bidirectional"))
    )
    (net (code "77") (name "unconnected-(U$1B-PD13-PadP$32)") (class "Default")
      (node (ref "U$1") (pin "P$32") (pinfunction "PD13_P$32") (pintype "bidirectional"))
    )
    (net (code "78") (name "unconnected-(U$1B-PD14-PadP$33)") (class "Default")
      (node (ref "U$1") (pin "P$33") (pinfunction "PD14_P$33") (pintype "bidirectional"))
    )
    (net (code "79") (name "unconnected-(U$1B-PD15-PadP$34)") (class "Default")
      (node (ref "U$1") (pin "P$34") (pinfunction "PD15_P$34") (pintype "bidirectional"))
    )
    (net (code "80") (name "unconnected-(U$1C-PB4-PadP$54)") (class "Default")
      (node (ref "U$1") (pin "P$54") (pinfunction "PB4_P$54") (pintype "bidirectional"))
    )
    (net (code "81") (name "unconnected-(U$1C-PB5-PadP$55)") (class "Default")
      (node (ref "U$1") (pin "P$55") (pinfunction "PB5_P$55") (pintype "bidirectional"))
    )
    (net (code "82") (name "unconnected-(U$1C-PB6-PadP$56)") (class "Default")
      (node (ref "U$1") (pin "P$56") (pinfunction "PB6_P$56") (pintype "bidirectional"))
    )
    (net (code "83") (name "unconnected-(U$1C-PB7-PadP$57)") (class "Default")
      (node (ref "U$1") (pin "P$57") (pinfunction "PB7_P$57") (pintype "bidirectional"))
    )
    (net (code "84") (name "unconnected-(U$1C-PB8-PadP$58)") (class "Default")
      (node (ref "U$1") (pin "P$58") (pinfunction "PB8_P$58") (pintype "bidirectional"))
    )
    (net (code "85") (name "unconnected-(U$1C-PB9-PadP$59)") (class "Default")
      (node (ref "U$1") (pin "P$59") (pinfunction "PB9_P$59") (pintype "bidirectional"))
    )
    (net (code "86") (name "unconnected-(U$1C-PC10-PadP$45)") (class "Default")
      (node (ref "U$1") (pin "P$45") (pinfunction "PC10_P$45") (pintype "bidirectional"))
    )
    (net (code "87") (name "unconnected-(U$1C-PC11-PadP$46)") (class "Default")
      (node (ref "U$1") (pin "P$46") (pinfunction "PC11_P$46") (pintype "bidirectional"))
    )
    (net (code "88") (name "unconnected-(U$1C-PC12-PadP$47)") (class "Default")
      (node (ref "U$1") (pin "P$47") (pinfunction "PC12_P$47") (pintype "bidirectional"))
    )
    (net (code "89") (name "unconnected-(U$1C-PD2-PadP$48)") (class "Default")
      (node (ref "U$1") (pin "P$48") (pinfunction "PD2_P$48") (pintype "bidirectional"))
    )
    (net (code "90") (name "unconnected-(U$1C-PD3-PadP$49)") (class "Default")
      (node (ref "U$1") (pin "P$49") (pinfunction "PD3_P$49") (pintype "bidirectional"))
    )
    (net (code "91") (name "unconnected-(U$1C-PD4-PadP$50)") (class "Default")
      (node (ref "U$1") (pin "P$50") (pinfunction "PD4_P$50") (pintype "bidirectional"))
    )
    (net (code "92") (name "unconnected-(U$1C-PD5-PadP$51)") (class "Default")
      (node (ref "U$1") (pin "P$51") (pinfunction "PD5_P$51") (pintype "bidirectional"))
    )
    (net (code "93") (name "unconnected-(U$1C-PD6-PadP$52)") (class "Default")
      (node (ref "U$1") (pin "P$52") (pinfunction "PD6_P$52") (pintype "bidirectional"))
    )
    (net (code "94") (name "unconnected-(U$1C-PD7-PadP$53)") (class "Default")
      (node (ref "U$1") (pin "P$53") (pinfunction "PD7_P$53") (pintype "bidirectional"))
    )
    (net (code "95") (name "unconnected-(U$1C-PE0-PadP$60)") (class "Default")
      (node (ref "U$1") (pin "P$60") (pinfunction "PE0_P$60") (pintype "bidirectional"))
    )
    (net (code "96") (name "unconnected-(U$1C-PE1-PadP$61)") (class "Default")
      (node (ref "U$1") (pin "P$61") (pinfunction "PE1_P$61") (pintype "bidirectional"))
    )
    (net (code "97") (name "unconnected-(U$1D-PA0-PadP$75)") (class "Default")
      (node (ref "U$1") (pin "P$75") (pinfunction "PA0_P$75") (pintype "bidirectional"))
    )
    (net (code "98") (name "unconnected-(U$1D-PA1-PadP$76)") (class "Default")
      (node (ref "U$1") (pin "P$76") (pinfunction "PA1_P$76") (pintype "bidirectional"))
    )
    (net (code "99") (name "unconnected-(U$1D-PA2-PadP$77)") (class "Default")
      (node (ref "U$1") (pin "P$77") (pinfunction "PA2_P$77") (pintype "bidirectional"))
    )
    (net (code "100") (name "unconnected-(U$1D-PC0-PadP$71)") (class "Default")
      (node (ref "U$1") (pin "P$71") (pinfunction "PC0_P$71") (pintype "bidirectional"))
    )
    (net (code "101") (name "unconnected-(U$1D-PC1-PadP$72)") (class "Default")
      (node (ref "U$1") (pin "P$72") (pinfunction "PC1_P$72") (pintype "bidirectional"))
    )
    (net (code "102") (name "unconnected-(U$1D-PC13-PadP$68)") (class "Default")
      (node (ref "U$1") (pin "P$68") (pinfunction "PC13_P$68") (pintype "bidirectional"))
    )
    (net (code "103") (name "unconnected-(U$1D-PE2-PadP$63)") (class "Default")
      (node (ref "U$1") (pin "P$63") (pinfunction "PE2_P$63") (pintype "bidirectional"))
    )
    (net (code "104") (name "unconnected-(U$1D-PE3-PadP$64)") (class "Default")
      (node (ref "U$1") (pin "P$64") (pinfunction "PE3_P$64") (pintype "bidirectional"))
    )
    (net (code "105") (name "unconnected-(U$1D-PE4-PadP$65)") (class "Default")
      (node (ref "U$1") (pin "P$65") (pinfunction "PE4_P$65") (pintype "bidirectional"))
    )
    (net (code "106") (name "unconnected-(U$1D-PE5-PadP$66)") (class "Default")
      (node (ref "U$1") (pin "P$66") (pinfunction "PE5_P$66") (pintype "bidirectional"))
    )
    (net (code "107") (name "unconnected-(U$1D-PE6-PadP$67)") (class "Default")
      (node (ref "U$1") (pin "P$67") (pinfunction "PE6_P$67") (pintype "bidirectional"))
    )
    (net (code "108") (name "unconnected-(U2-NC-Pad4)") (class "Default")
      (node (ref "U2") (pin "4") (pinfunction "NC_4") (pintype "no_connect"))
    )
    (net (code "109") (name "unconnected-(U3-NC-Pad4)") (class "Default")
      (node (ref "U3") (pin "4") (pinfunction "NC_4") (pintype "no_connect"))
    )
  )
)
